# avrBetterSTK200.net
KiCad netlist of a schematic drawn in EAGLE
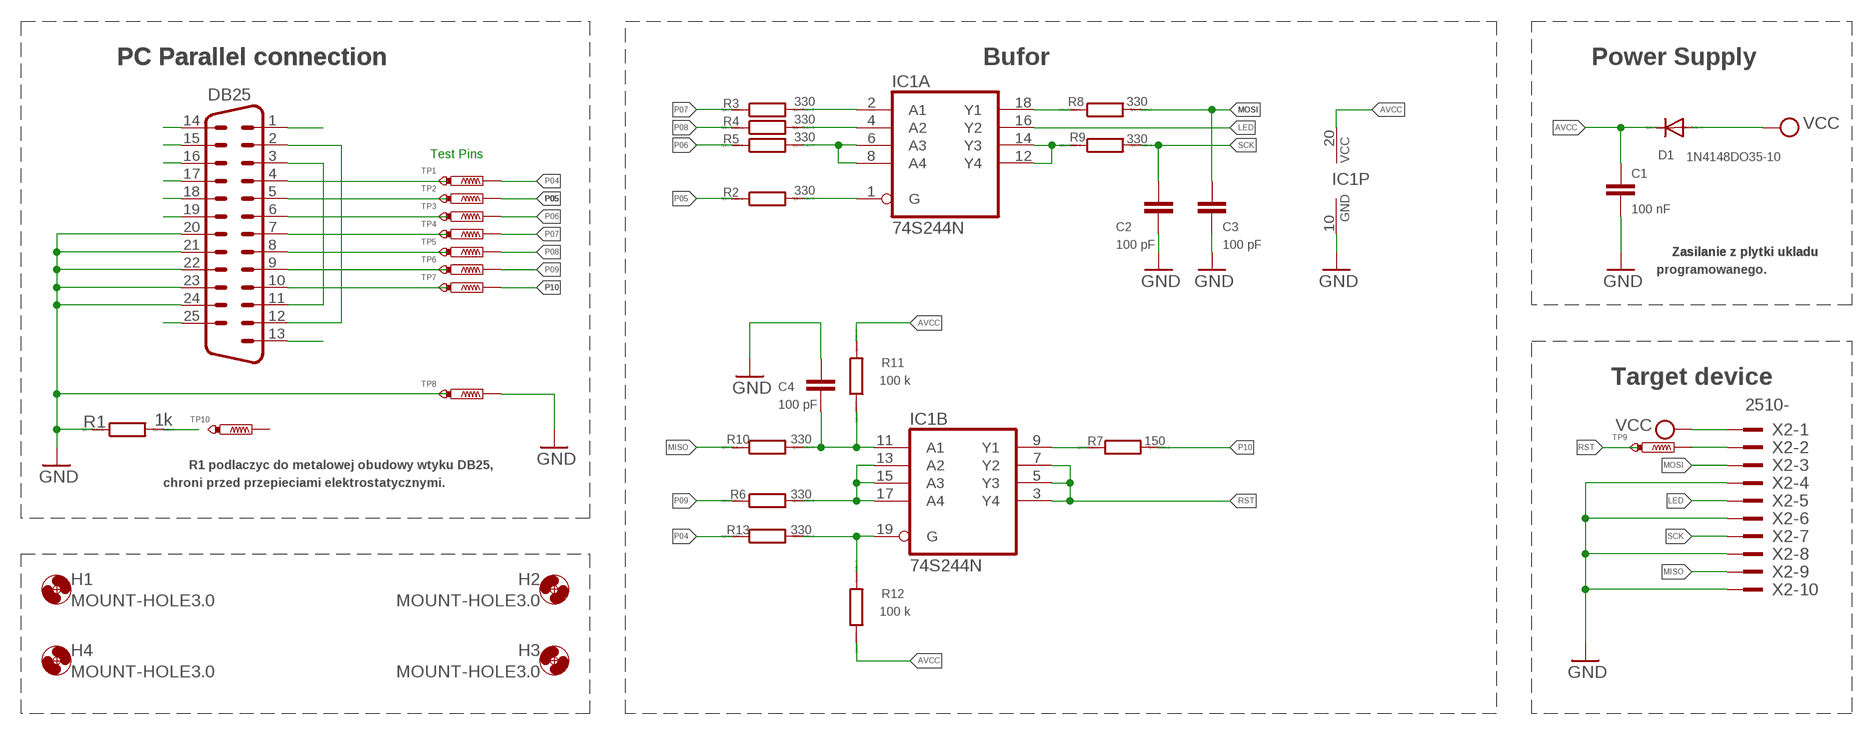
[diagram p0: schematic, sheet 1]

(export (version "E")
  (design (tool "Eeschema 10.0.6"))
  (components
    (comp (ref "C1")
      (value "100 nF")
      (footprint "eagle-import:C050-035X075")
      (libsource (lib "eagle-import") (part "C-EU050-035X075"))
    )
    (comp (ref "C2")
      (value "100 pF")
      (footprint "eagle-import:C050-035X075")
      (libsource (lib "eagle-import") (part "C-EU050-035X075"))
    )
    (comp (ref "C3")
      (value "100 pF")
      (footprint "eagle-import:C050-035X075")
      (libsource (lib "eagle-import") (part "C-EU050-035X075"))
    )
    (comp (ref "C4")
      (value "100 pF")
      (footprint "eagle-import:C050-035X075")
      (libsource (lib "eagle-import") (part "C-EU050-035X075"))
    )
    (comp (ref "D1")
      (value "1N4148DO35-10")
      (footprint "eagle-import:DO35-10")
      (libsource (lib "eagle-import") (part "1N4148DO35-10"))
    )
    (comp (ref "DB25")
      (value "M25V")
      (footprint "eagle-import:M25V")
      (libsource (lib "eagle-import") (part "M25V"))
    )
    (comp (ref "H1")
      (value "MOUNT-HOLE3.0")
      (footprint "eagle-import:3,0")
      (libsource (lib "eagle-import") (part "MOUNT-HOLE3.0"))
    )
    (comp (ref "H2")
      (value "MOUNT-HOLE3.0")
      (footprint "eagle-import:3,0")
      (libsource (lib "eagle-import") (part "MOUNT-HOLE3.0"))
    )
    (comp (ref "H3")
      (value "MOUNT-HOLE3.0")
      (footprint "eagle-import:3,0")
      (libsource (lib "eagle-import") (part "MOUNT-HOLE3.0"))
    )
    (comp (ref "H4")
      (value "MOUNT-HOLE3.0")
      (footprint "eagle-import:3,0")
      (libsource (lib "eagle-import") (part "MOUNT-HOLE3.0"))
    )
    (comp (ref "IC1")
      (value "74S244N")
      (footprint "eagle-import:DIL20")
      (libsource (lib "eagle-import") (part "74244NS"))
    )
    (comp (ref "R1")
      (value "1k")
      (footprint "eagle-import:0207_10")
      (libsource (lib "eagle-import") (part "R-EU_0207_10"))
    )
    (comp (ref "R2")
      (value "330")
      (footprint "eagle-import:0207_10")
      (libsource (lib "eagle-import") (part "R-EU_0207_10"))
    )
    (comp (ref "R3")
      (value "330")
      (footprint "eagle-import:0207_10")
      (libsource (lib "eagle-import") (part "R-EU_0207_10"))
    )
    (comp (ref "R4")
      (value "330")
      (footprint "eagle-import:0207_10")
      (libsource (lib "eagle-import") (part "R-EU_0207_10"))
    )
    (comp (ref "R5")
      (value "330")
      (footprint "eagle-import:0207_10")
      (libsource (lib "eagle-import") (part "R-EU_0207_10"))
    )
    (comp (ref "R6")
      (value "330")
      (footprint "eagle-import:0207_10")
      (libsource (lib "eagle-import") (part "R-EU_0207_10"))
    )
    (comp (ref "R7")
      (value "150")
      (footprint "eagle-import:0207_10")
      (libsource (lib "eagle-import") (part "R-EU_0207_10"))
    )
    (comp (ref "R8")
      (value "330")
      (footprint "eagle-import:0207_10")
      (libsource (lib "eagle-import") (part "R-EU_0207_10"))
    )
    (comp (ref "R9")
      (value "330")
      (footprint "eagle-import:0207_10")
      (libsource (lib "eagle-import") (part "R-EU_0207_10"))
    )
    (comp (ref "R10")
      (value "330")
      (footprint "eagle-import:0207_10")
      (libsource (lib "eagle-import") (part "R-EU_0207_10"))
    )
    (comp (ref "R11")
      (value "100 k")
      (footprint "eagle-import:0207_10")
      (libsource (lib "eagle-import") (part "R-EU_0207_10"))
    )
    (comp (ref "R12")
      (value "100 k")
      (footprint "eagle-import:0207_10")
      (libsource (lib "eagle-import") (part "R-EU_0207_10"))
    )
    (comp (ref "R13")
      (value "330")
      (footprint "eagle-import:0207_10")
      (libsource (lib "eagle-import") (part "R-EU_0207_10"))
    )
    (comp (ref "TP1")
      (value "PTR1PAD1-17Y")
      (footprint "eagle-import:P1-17Y")
      (libsource (lib "eagle-import") (part "PTR1PAD1-17Y"))
    )
    (comp (ref "TP2")
      (value "PTR1PAD1-17Y")
      (footprint "eagle-import:P1-17Y")
      (libsource (lib "eagle-import") (part "PTR1PAD1-17Y"))
    )
    (comp (ref "TP3")
      (value "PTR1PAD1-17Y")
      (footprint "eagle-import:P1-17Y")
      (libsource (lib "eagle-import") (part "PTR1PAD1-17Y"))
    )
    (comp (ref "TP4")
      (value "PTR1PAD1-17Y")
      (footprint "eagle-import:P1-17Y")
      (libsource (lib "eagle-import") (part "PTR1PAD1-17Y"))
    )
    (comp (ref "TP5")
      (value "PTR1PAD1-17Y")
      (footprint "eagle-import:P1-17Y")
      (libsource (lib "eagle-import") (part "PTR1PAD1-17Y"))
    )
    (comp (ref "TP6")
      (value "PTR1PAD1-17Y")
      (footprint "eagle-import:P1-17Y")
      (libsource (lib "eagle-import") (part "PTR1PAD1-17Y"))
    )
    (comp (ref "TP7")
      (value "PTR1PAD1-17Y")
      (footprint "eagle-import:P1-17Y")
      (libsource (lib "eagle-import") (part "PTR1PAD1-17Y"))
    )
    (comp (ref "TP8")
      (value "PTR1PAD1-17Y")
      (footprint "eagle-import:P1-17Y")
      (libsource (lib "eagle-import") (part "PTR1PAD1-17Y"))
    )
    (comp (ref "TP9")
      (value "PTR1PAD1-17Y")
      (footprint "eagle-import:P1-17Y")
      (libsource (lib "eagle-import") (part "PTR1PAD1-17Y"))
    )
    (comp (ref "TP10")
      (value "PTR1PAD1-17Y")
      (footprint "eagle-import:P1-17Y")
      (libsource (lib "eagle-import") (part "PTR1PAD1-17Y"))
    )
    (comp (ref "X2")
      (value "2510-")
      (footprint "eagle-import:PAK100_2500-10")
      (fields (field (name "MF") "3M") (field (name "MPN") "2510-6002UB"))
      (libsource (lib "eagle-import") (part "2510-"))
    )
  )
  (nets
    (net (code "1") (name "AVCC") (class "Default")
      (node (ref "C1") (pin "1") (pinfunction "1_1") (pintype "passive"))
      (node (ref "D1") (pin "C") (pinfunction "C_C") (pintype "passive"))
      (node (ref "IC1") (pin "20") (pinfunction "VCC_20") (pintype "power_in"))
      (node (ref "R11") (pin "2") (pinfunction "2_2") (pintype "passive"))
      (node (ref "R12") (pin "1") (pinfunction "1_1") (pintype "passive"))
    )
    (net (code "2") (name "GND") (class "Default")
      (node (ref "C1") (pin "2") (pinfunction "2_2") (pintype "passive"))
      (node (ref "C2") (pin "2") (pinfunction "2_2") (pintype "passive"))
      (node (ref "C3") (pin "2") (pinfunction "2_2") (pintype "passive"))
      (node (ref "C4") (pin "1") (pinfunction "1_1") (pintype "passive"))
      (node (ref "DB25") (pin "20") (pinfunction "20_20") (pintype "passive"))
      (node (ref "DB25") (pin "21") (pinfunction "21_21") (pintype "passive"))
      (node (ref "DB25") (pin "22") (pinfunction "22_22") (pintype "passive"))
      (node (ref "DB25") (pin "23") (pinfunction "23_23") (pintype "passive"))
      (node (ref "DB25") (pin "24") (pinfunction "24_24") (pintype "passive"))
      (node (ref "IC1") (pin "10") (pinfunction "GND_10") (pintype "power_in"))
      (node (ref "R1") (pin "1") (pinfunction "1_1") (pintype "passive"))
      (node (ref "TP8") (pin "TP") (pinfunction "TP_TP") (pintype "input"))
      (node (ref "X2") (pin "10") (pinfunction "KL_10") (pintype "passive"))
      (node (ref "X2") (pin "4") (pinfunction "KL_4") (pintype "passive"))
      (node (ref "X2") (pin "6") (pinfunction "KL_6") (pintype "passive"))
      (node (ref "X2") (pin "8") (pinfunction "KL_8") (pintype "passive"))
    )
    (net (code "3") (name "LED") (class "Default")
      (node (ref "IC1") (pin "16") (pinfunction "Y2_16") (pintype "tri_state"))
      (node (ref "X2") (pin "5") (pinfunction "KL_5") (pintype "passive"))
    )
    (net (code "4") (name "MISO") (class "Default")
      (node (ref "R10") (pin "1") (pinfunction "1_1") (pintype "passive"))
      (node (ref "X2") (pin "9") (pinfunction "KL_9") (pintype "passive"))
    )
    (net (code "5") (name "MOSI") (class "Default")
      (node (ref "C3") (pin "1") (pinfunction "1_1") (pintype "passive"))
      (node (ref "R8") (pin "2") (pinfunction "2_2") (pintype "passive"))
      (node (ref "X2") (pin "3") (pinfunction "KL_3") (pintype "passive"))
    )
    (net (code "6") (name "Net-(DB25-Pad11)") (class "Default")
      (node (ref "DB25") (pin "11") (pinfunction "11_11") (pintype "passive"))
      (node (ref "DB25") (pin "3") (pinfunction "3_3") (pintype "passive"))
    )
    (net (code "7") (name "Net-(DB25-Pad12)") (class "Default")
      (node (ref "DB25") (pin "12") (pinfunction "12_12") (pintype "passive"))
      (node (ref "DB25") (pin "2") (pinfunction "2_2") (pintype "passive"))
    )
    (net (code "8") (name "Net-(IC1A-A1)") (class "Default")
      (node (ref "IC1") (pin "2") (pinfunction "A1_2") (pintype "input"))
      (node (ref "R3") (pin "2") (pinfunction "2_2") (pintype "passive"))
    )
    (net (code "9") (name "Net-(IC1A-A2)") (class "Default")
      (node (ref "IC1") (pin "4") (pinfunction "A2_4") (pintype "input"))
      (node (ref "R4") (pin "2") (pinfunction "2_2") (pintype "passive"))
    )
    (net (code "10") (name "Net-(IC1A-A3)") (class "Default")
      (node (ref "IC1") (pin "6") (pinfunction "A3_6") (pintype "input"))
      (node (ref "IC1") (pin "8") (pinfunction "A4_8") (pintype "input"))
      (node (ref "R5") (pin "2") (pinfunction "2_2") (pintype "passive"))
    )
    (net (code "11") (name "Net-(IC1A-G)") (class "Default")
      (node (ref "IC1") (pin "1") (pinfunction "G_1") (pintype "input"))
      (node (ref "R2") (pin "2") (pinfunction "2_2") (pintype "passive"))
    )
    (net (code "12") (name "Net-(IC1A-Y1)") (class "Default")
      (node (ref "IC1") (pin "18") (pinfunction "Y1_18") (pintype "tri_state"))
      (node (ref "R8") (pin "1") (pinfunction "1_1") (pintype "passive"))
    )
    (net (code "13") (name "Net-(IC1A-Y3)") (class "Default")
      (node (ref "IC1") (pin "12") (pinfunction "Y4_12") (pintype "tri_state"))
      (node (ref "IC1") (pin "14") (pinfunction "Y3_14") (pintype "tri_state"))
      (node (ref "R9") (pin "1") (pinfunction "1_1") (pintype "passive"))
    )
    (net (code "14") (name "Net-(IC1B-A1)") (class "Default")
      (node (ref "C4") (pin "2") (pinfunction "2_2") (pintype "passive"))
      (node (ref "IC1") (pin "11") (pinfunction "A1_11") (pintype "input"))
      (node (ref "R10") (pin "2") (pinfunction "2_2") (pintype "passive"))
      (node (ref "R11") (pin "1") (pinfunction "1_1") (pintype "passive"))
    )
    (net (code "15") (name "Net-(IC1B-A2)") (class "Default")
      (node (ref "IC1") (pin "13") (pinfunction "A2_13") (pintype "input"))
      (node (ref "IC1") (pin "15") (pinfunction "A3_15") (pintype "input"))
      (node (ref "IC1") (pin "17") (pinfunction "A4_17") (pintype "input"))
      (node (ref "R6") (pin "2") (pinfunction "2_2") (pintype "passive"))
    )
    (net (code "16") (name "Net-(IC1B-G)") (class "Default")
      (node (ref "IC1") (pin "19") (pinfunction "G_19") (pintype "input"))
      (node (ref "R12") (pin "2") (pinfunction "2_2") (pintype "passive"))
      (node (ref "R13") (pin "2") (pinfunction "2_2") (pintype "passive"))
    )
    (net (code "17") (name "Net-(IC1B-Y1)") (class "Default")
      (node (ref "IC1") (pin "9") (pinfunction "Y1_9") (pintype "tri_state"))
      (node (ref "R7") (pin "1") (pinfunction "1_1") (pintype "passive"))
    )
    (net (code "18") (name "P04") (class "Default")
      (node (ref "R13") (pin "1") (pinfunction "1_1") (pintype "passive"))
      (node (ref "TP1") (pin "TP") (pinfunction "TP_TP") (pintype "input"))
    )
    (net (code "19") (name "P05") (class "Default")
      (node (ref "R2") (pin "1") (pinfunction "1_1") (pintype "passive"))
      (node (ref "TP2") (pin "TP") (pinfunction "TP_TP") (pintype "input"))
    )
    (net (code "20") (name "P06") (class "Default")
      (node (ref "R5") (pin "1") (pinfunction "1_1") (pintype "passive"))
      (node (ref "TP3") (pin "TP") (pinfunction "TP_TP") (pintype "input"))
    )
    (net (code "21") (name "P07") (class "Default")
      (node (ref "R3") (pin "1") (pinfunction "1_1") (pintype "passive"))
      (node (ref "TP4") (pin "TP") (pinfunction "TP_TP") (pintype "input"))
    )
    (net (code "22") (name "P08") (class "Default")
      (node (ref "R4") (pin "1") (pinfunction "1_1") (pintype "passive"))
      (node (ref "TP5") (pin "TP") (pinfunction "TP_TP") (pintype "input"))
    )
    (net (code "23") (name "P09") (class "Default")
      (node (ref "R6") (pin "1") (pinfunction "1_1") (pintype "passive"))
      (node (ref "TP6") (pin "TP") (pinfunction "TP_TP") (pintype "input"))
    )
    (net (code "24") (name "P10") (class "Default")
      (node (ref "R7") (pin "2") (pinfunction "2_2") (pintype "passive"))
      (node (ref "TP7") (pin "TP") (pinfunction "TP_TP") (pintype "input"))
    )
    (net (code "25") (name "RST") (class "Default")
      (node (ref "IC1") (pin "3") (pinfunction "Y4_3") (pintype "tri_state"))
      (node (ref "IC1") (pin "5") (pinfunction "Y3_5") (pintype "tri_state"))
      (node (ref "IC1") (pin "7") (pinfunction "Y2_7") (pintype "tri_state"))
      (node (ref "TP9") (pin "TP") (pinfunction "TP_TP") (pintype "input"))
      (node (ref "X2") (pin "2") (pinfunction "KL_2") (pintype "passive"))
    )
    (net (code "26") (name "SCK") (class "Default")
      (node (ref "C2") (pin "1") (pinfunction "1_1") (pintype "passive"))
      (node (ref "R9") (pin "2") (pinfunction "2_2") (pintype "passive"))
      (node (ref "X2") (pin "7") (pinfunction "KL_7") (pintype "passive"))
    )
    (net (code "27") (name "VCC") (class "Default")
      (node (ref "D1") (pin "A") (pinfunction "A_A") (pintype "passive"))
      (node (ref "X2") (pin "1") (pinfunction "KL_1") (pintype "passive"))
    )
    (net (code "28") (name "unconnected-(DB25-Pad1)") (class "Default")
      (node (ref "DB25") (pin "1") (pinfunction "1_1") (pintype "passive"))
    )
    (net (code "29") (name "unconnected-(DB25-Pad4)") (class "Default")
      (node (ref "DB25") (pin "4") (pinfunction "4_4") (pintype "passive"))
    )
    (net (code "30") (name "unconnected-(DB25-Pad5)") (class "Default")
      (node (ref "DB25") (pin "5") (pinfunction "5_5") (pintype "passive"))
    )
    (net (code "31") (name "unconnected-(DB25-Pad6)") (class "Default")
      (node (ref "DB25") (pin "6") (pinfunction "6_6") (pintype "passive"))
    )
    (net (code "32") (name "unconnected-(DB25-Pad7)") (class "Default")
      (node (ref "DB25") (pin "7") (pinfunction "7_7") (pintype "passive"))
    )
    (net (code "33") (name "unconnected-(DB25-Pad8)") (class "Default")
      (node (ref "DB25") (pin "8") (pinfunction "8_8") (pintype "passive"))
    )
    (net (code "34") (name "unconnected-(DB25-Pad9)") (class "Default")
      (node (ref "DB25") (pin "9") (pinfunction "9_9") (pintype "passive"))
    )
    (net (code "35") (name "unconnected-(DB25-Pad10)") (class "Default")
      (node (ref "DB25") (pin "10") (pinfunction "10_10") (pintype "passive"))
    )
    (net (code "36") (name "unconnected-(DB25-Pad13)") (class "Default")
      (node (ref "DB25") (pin "13") (pinfunction "13_13") (pintype "passive"))
    )
    (net (code "37") (name "unconnected-(DB25-Pad14)") (class "Default")
      (node (ref "DB25") (pin "14") (pinfunction "14_14") (pintype "passive"))
    )
    (net (code "38") (name "unconnected-(DB25-Pad15)") (class "Default")
      (node (ref "DB25") (pin "15") (pinfunction "15_15") (pintype "passive"))
    )
    (net (code "39") (name "unconnected-(DB25-Pad16)") (class "Default")
      (node (ref "DB25") (pin "16") (pinfunction "16_16") (pintype "passive"))
    )
    (net (code "40") (name "unconnected-(DB25-Pad17)") (class "Default")
      (node (ref "DB25") (pin "17") (pinfunction "17_17") (pintype "passive"))
    )
    (net (code "41") (name "unconnected-(DB25-Pad18)") (class "Default")
      (node (ref "DB25") (pin "18") (pinfunction "18_18") (pintype "passive"))
    )
    (net (code "42") (name "unconnected-(DB25-Pad19)") (class "Default")
      (node (ref "DB25") (pin "19") (pinfunction "19_19") (pintype "passive"))
    )
    (net (code "43") (name "unconnected-(DB25-Pad25)") (class "Default")
      (node (ref "DB25") (pin "25") (pinfunction "25_25") (pintype "passive"))
    )
    (net (code "44") (name "unconnected-(R1-Pad2)") (class "Default")
      (node (ref "R1") (pin "2") (pinfunction "2_2") (pintype "passive"))
    )
    (net (code "45") (name "unconnected-(TP10-PadTP)") (class "Default")
      (node (ref "TP10") (pin "TP") (pinfunction "TP_TP") (pintype "input"))
    )
  )
)
